# MCU.net
KiCad netlist of a schematic drawn in Altium Designer
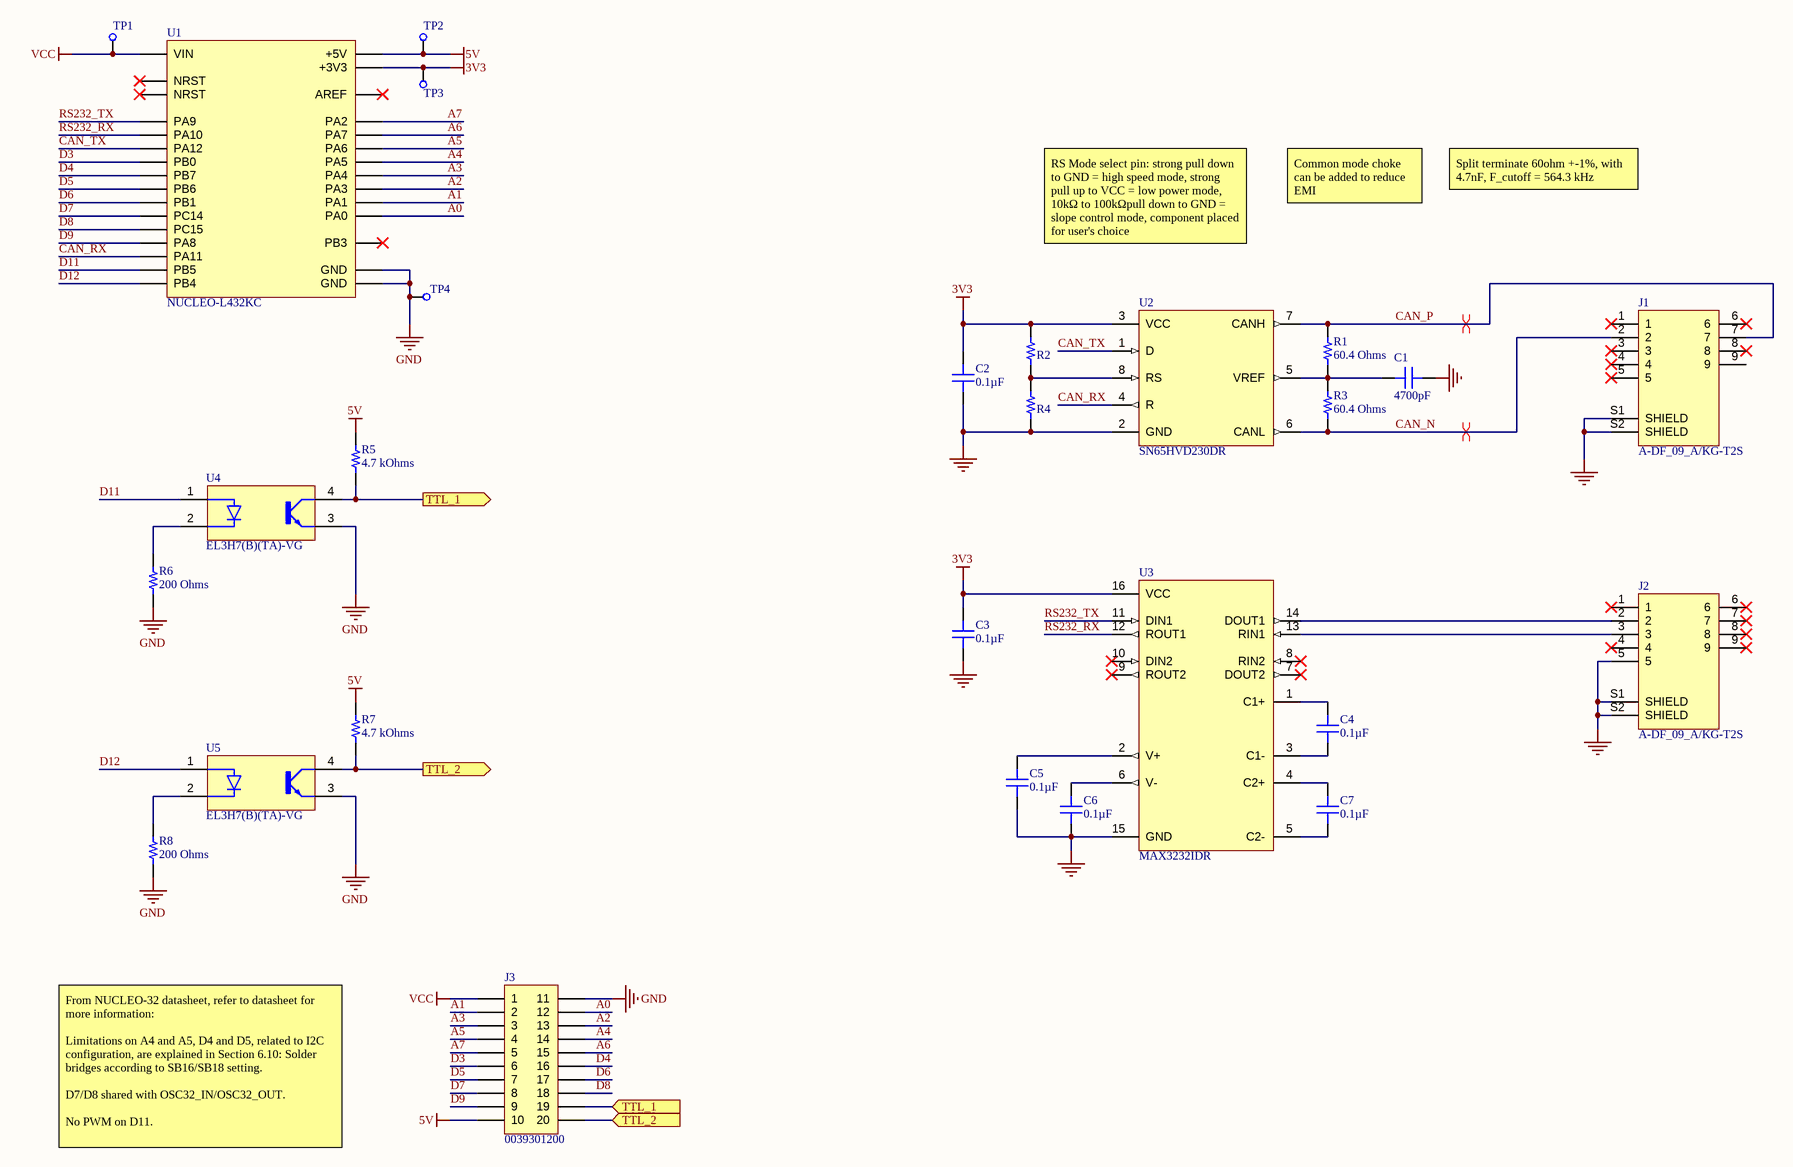
[diagram p0: MCU.SchDoc]

(export (version "E")
  (design (tool "Eeschema 10.0.6"))
  (components
    (comp (ref "C1")
      (value "4700pF")
      (footprint "CAP 0603_1608")
      (description "CAP CER 4700PF 50V X7R 0603")
      (fields
        (field (name "PART NUMBER") "CGA3E2X7R1H472K080AA")
        (field (name "MANUFACTURER") "TDK Corporation")
      )
      (libsource (lib "Celestial Altium Library - altium_library") (part "Capacitor"))
    )
    (comp (ref "C2")
      (value "0.1µF")
      (footprint "CAP 0603_1608")
      (description "CAP CER 0.1UF 25V X7R 0603")
      (fields
        (field (name "PART NUMBER") "CL10B104KA8NNNC")
        (field (name "MANUFACTURER") "Samsung Electro-Mechanics")
      )
      (libsource (lib "Celestial Altium Library - altium_library") (part "Capacitor"))
    )
    (comp (ref "C3")
      (value "0.1µF")
      (footprint "CAP 0603_1608")
      (description "CAP CER 0.1UF 25V X7R 0603")
      (fields
        (field (name "PART NUMBER") "CL10B104KA8NNNC")
        (field (name "MANUFACTURER") "Samsung Electro-Mechanics")
      )
      (libsource (lib "Celestial Altium Library - altium_library") (part "Capacitor"))
    )
    (comp (ref "C4")
      (value "0.1µF")
      (footprint "CAP 0603_1608")
      (description "CAP CER 0.1UF 25V X7R 0603")
      (fields
        (field (name "PART NUMBER") "CL10B104KA8NNNC")
        (field (name "MANUFACTURER") "Samsung Electro-Mechanics")
      )
      (libsource (lib "Celestial Altium Library - altium_library") (part "Capacitor"))
    )
    (comp (ref "C5")
      (value "0.1µF")
      (footprint "CAP 0603_1608")
      (description "CAP CER 0.1UF 25V X7R 0603")
      (fields
        (field (name "PART NUMBER") "CL10B104KA8NNNC")
        (field (name "MANUFACTURER") "Samsung Electro-Mechanics")
      )
      (libsource (lib "Celestial Altium Library - altium_library") (part "Capacitor"))
    )
    (comp (ref "C6")
      (value "0.1µF")
      (footprint "CAP 0603_1608")
      (description "CAP CER 0.1UF 25V X7R 0603")
      (fields
        (field (name "PART NUMBER") "CL10B104KA8NNNC")
        (field (name "MANUFACTURER") "Samsung Electro-Mechanics")
      )
      (libsource (lib "Celestial Altium Library - altium_library") (part "Capacitor"))
    )
    (comp (ref "C7")
      (value "0.1µF")
      (footprint "CAP 0603_1608")
      (description "CAP CER 0.1UF 25V X7R 0603")
      (fields
        (field (name "PART NUMBER") "CL10B104KA8NNNC")
        (field (name "MANUFACTURER") "Samsung Electro-Mechanics")
      )
      (libsource (lib "Celestial Altium Library - altium_library") (part "Capacitor"))
    )
    (comp (ref "J1")
      (value "A-DF_09_A/KG-T2S")
      (footprint "ASSMANN_A-DF09A/KG-T2S")
      (description "Conn D-Subminiature F 9 POS 2.77mm Solder RA Thru-Hole 9 Terminal 1 Port")
      (fields (field (name "MF") "{'manufacturer': u'Assmann WSW'}"))
      (libsource (lib "RTC_Mini_Symbols") (part "A-DF_09_A/KG-T2S"))
    )
    (comp (ref "J2")
      (value "A-DF_09_A/KG-T2S")
      (footprint "ASSMANN_A-DF09A/KG-T2S")
      (description "Conn D-Subminiature F 9 POS 2.77mm Solder RA Thru-Hole 9 Terminal 1 Port")
      (fields (field (name "MF") "{'manufacturer': u'Assmann WSW'}"))
      (libsource (lib "RTC_Mini_Symbols") (part "A-DF_09_A/KG-T2S"))
    )
    (comp (ref "J3")
      (value "0039301200")
      (footprint "MOLEX_0039301200")
      (description "Connector Header Through Hole, Right Angle 20 position 0.165\" (4.20mm)")
      (libsource (lib "RTC_Mini_Symbols") (part "0039301200"))
    )
    (comp (ref "R1")
      (value "60.4 Ohms")
      (footprint "RES 0603_1608")
      (description "RES 60.4 OHM 1% 1/10W 0603")
      (fields
        (field (name "PART NUMBER") "RMCF0603FT60R4")
        (field (name "MANUFACTURER") "Stackpole Electronics Inc")
      )
      (libsource (lib "Celestial Altium Library - altium_library") (part "Resistor"))
    )
    (comp (ref "R2")
      (value "~")
      (footprint "RES 0805_2012")
      (description "RES SMD 0 OHM JUMP 1/8W 0805")
      (fields (field (name "PART NUMBER") "CRCW08050000Z0EAC") (field (name "MANUFACTURER") "Vishay Dale"))
      (libsource (lib "Celestial Altium Library - altium_library") (part "Resistor"))
    )
    (comp (ref "R3")
      (value "60.4 Ohms")
      (footprint "RES 0603_1608")
      (description "RES 60.4 OHM 1% 1/10W 0603")
      (fields
        (field (name "PART NUMBER") "RMCF0603FT60R4")
        (field (name "MANUFACTURER") "Stackpole Electronics Inc")
      )
      (libsource (lib "Celestial Altium Library - altium_library") (part "Resistor"))
    )
    (comp (ref "R4")
      (value "~")
      (footprint "RES 0805_2012")
      (description "RES SMD 0 OHM JUMP 1/8W 0805")
      (fields (field (name "PART NUMBER") "CRCW08050000Z0EAC") (field (name "MANUFACTURER") "Vishay Dale"))
      (libsource (lib "Celestial Altium Library - altium_library") (part "Resistor"))
    )
    (comp (ref "R5")
      (value "4.7 kOhms")
      (footprint "RES 0603_1608")
      (description "RES SMD 4.7K OHM 1% 1/10W 0603")
      (fields (field (name "PART NUMBER") "RC0603FR-074K7L") (field (name "MANUFACTURER") "Yageo"))
      (libsource (lib "Celestial Altium Library - altium_library") (part "Resistor"))
    )
    (comp (ref "R6")
      (value "200 Ohms")
      (footprint "RES 0603_1608")
      (description "RES 200 OHM 5% 1/10W 0603")
      (fields
        (field (name "PART NUMBER") "RMCF0603JT200R")
        (field (name "MANUFACTURER") "Stackpole Electronics Inc")
      )
      (libsource (lib "Celestial Altium Library - altium_library") (part "Resistor"))
    )
    (comp (ref "R7")
      (value "4.7 kOhms")
      (footprint "RES 0603_1608")
      (description "RES SMD 4.7K OHM 1% 1/10W 0603")
      (fields (field (name "PART NUMBER") "RC0603FR-074K7L") (field (name "MANUFACTURER") "Yageo"))
      (libsource (lib "Celestial Altium Library - altium_library") (part "Resistor"))
    )
    (comp (ref "R8")
      (value "200 Ohms")
      (footprint "RES 0603_1608")
      (description "RES 200 OHM 5% 1/10W 0603")
      (fields
        (field (name "PART NUMBER") "RMCF0603JT200R")
        (field (name "MANUFACTURER") "Stackpole Electronics Inc")
      )
      (libsource (lib "Celestial Altium Library - altium_library") (part "Resistor"))
    )
    (comp (ref "TP1")
      (value "Testpoint1")
      (footprint "TESTPOINT40")
      (description "Testpoint 40mil pad")
      (libsource (lib "RTC_Mini_Symbols") (part "Testpoint1"))
    )
    (comp (ref "TP2")
      (value "Testpoint1")
      (footprint "TESTPOINT40")
      (description "Testpoint 40mil pad")
      (libsource (lib "RTC_Mini_Symbols") (part "Testpoint1"))
    )
    (comp (ref "TP3")
      (value "Testpoint1")
      (footprint "TESTPOINT40")
      (description "Testpoint 40mil pad")
      (libsource (lib "RTC_Mini_Symbols") (part "Testpoint1"))
    )
    (comp (ref "TP4")
      (value "Testpoint1")
      (footprint "TESTPOINT40")
      (description "Testpoint 40mil pad")
      (libsource (lib "RTC_Mini_Symbols") (part "Testpoint1"))
    )
    (comp (ref "U1")
      (value "NUCLEO-L432KC")
      (footprint "MODULE_NUCLEO-L432KC")
      (description "STM32 Nucleo-32 development board with STM32L432KC MCU, supports Arduino connectivity")
      (fields (field (name "MF") "{'manufacturer': u'STMicroelectronics'}"))
      (libsource (lib "RTC_Mini_Symbols") (part "NUCLEO-L432KC"))
    )
    (comp (ref "U2")
      (value "SN65HVD230DR")
      (footprint "SOIC127P599X175-8N")
      (description "3.3 V CAN Transceiver with Standby Mode 8-SOIC -40 to 85")
      (fields (field (name "MF") "{'manufacturer': u'Texas Instruments'}"))
      (libsource (lib "RTC_Mini_Symbols") (part "SN65HVD230DR"))
    )
    (comp (ref "U3")
      (value "MAX3232IDR")
      (footprint "SOIC127P600X175-16N")
      (description "3-V to 5.5-V multichannel RS-232 line driver & receiver 16-SOIC -40 to 85")
      (fields (field (name "MF") "{'manufacturer': u'Texas Instruments'}"))
      (libsource (lib "RTC_Mini_Symbols") (part "MAX3232IDR"))
    )
    (comp (ref "U4")
      (value "EL3H7(B)(TA)-VG")
      (footprint "SOIC127P700X200-4N")
      (description "Optoisolator Transistor Output 3750Vrms 1 Channel 4-SSOP")
      (fields (field (name "MP") "EL3H7-G") (field (name "MF") "{'manufacturer': u'Everlight Electronics'}"))
      (libsource (lib "RTC_Mini_Symbols") (part "EL3H7(B)(TA)-VG"))
    )
    (comp (ref "U5")
      (value "EL3H7(B)(TA)-VG")
      (footprint "SOIC127P700X200-4N")
      (description "Optoisolator Transistor Output 3750Vrms 1 Channel 4-SSOP")
      (fields (field (name "MP") "EL3H7-G") (field (name "MF") "{'manufacturer': u'Everlight Electronics'}"))
      (libsource (lib "RTC_Mini_Symbols") (part "EL3H7(B)(TA)-VG"))
    )
  )
  (nets
    (net (code "1") (name "/A0") (class "Default")
      (node (ref "J3") (pin "12") (pinfunction "12_12") (pintype "passive"))
      (node (ref "U1") (pin "CN4_12") (pinfunction "PA0_CN4_12") (pintype "passive"))
    )
    (net (code "2") (name "/A1") (class "Default")
      (node (ref "J3") (pin "2") (pinfunction "2_2") (pintype "passive"))
      (node (ref "U1") (pin "CN4_11") (pinfunction "PA1_CN4_11") (pintype "passive"))
    )
    (net (code "3") (name "/A2") (class "Default")
      (node (ref "J3") (pin "13") (pinfunction "13_13") (pintype "passive"))
      (node (ref "U1") (pin "CN4_10") (pinfunction "PA3_CN4_10") (pintype "passive"))
    )
    (net (code "4") (name "/A3") (class "Default")
      (node (ref "J3") (pin "3") (pinfunction "3_3") (pintype "passive"))
      (node (ref "U1") (pin "CN4_9") (pinfunction "PA4_CN4_9") (pintype "passive"))
    )
    (net (code "5") (name "/A4") (class "Default")
      (node (ref "J3") (pin "14") (pinfunction "14_14") (pintype "passive"))
      (node (ref "U1") (pin "CN4_8") (pinfunction "PA5_CN4_8") (pintype "passive"))
    )
    (net (code "6") (name "/A5") (class "Default")
      (node (ref "J3") (pin "4") (pinfunction "4_4") (pintype "passive"))
      (node (ref "U1") (pin "CN4_7") (pinfunction "PA6_CN4_7") (pintype "passive"))
    )
    (net (code "7") (name "/A6") (class "Default")
      (node (ref "J3") (pin "15") (pinfunction "15_15") (pintype "passive"))
      (node (ref "U1") (pin "CN4_6") (pinfunction "PA7_CN4_6") (pintype "passive"))
    )
    (net (code "8") (name "/A7") (class "Default")
      (node (ref "J3") (pin "5") (pinfunction "5_5") (pintype "passive"))
      (node (ref "U1") (pin "CN4_5") (pinfunction "PA2_CN4_5") (pintype "passive"))
    )
    (net (code "9") (name "/CAN_N") (class "Default")
      (node (ref "J1") (pin "2") (pinfunction "2_2") (pintype "passive"))
      (node (ref "R3") (pin "2") (pinfunction "2_2") (pintype "passive"))
      (node (ref "U2") (pin "6") (pinfunction "CANL_6") (pintype "output"))
    )
    (net (code "10") (name "/CAN_P") (class "Default")
      (node (ref "J1") (pin "7") (pinfunction "7_7") (pintype "passive"))
      (node (ref "R1") (pin "1") (pinfunction "1_1") (pintype "passive"))
      (node (ref "U2") (pin "7") (pinfunction "CANH_7") (pintype "output"))
    )
    (net (code "11") (name "/CAN_RX") (class "Default")
      (node (ref "U1") (pin "CN3_13") (pinfunction "PA11_CN3_13") (pintype "passive"))
      (node (ref "U2") (pin "4") (pinfunction "R_4") (pintype "output"))
    )
    (net (code "12") (name "/CAN_TX") (class "Default")
      (node (ref "U1") (pin "CN3_5") (pinfunction "PA12_CN3_5") (pintype "passive"))
      (node (ref "U2") (pin "1") (pinfunction "D_1") (pintype "input"))
    )
    (net (code "13") (name "/D3") (class "Default")
      (node (ref "J3") (pin "6") (pinfunction "6_6") (pintype "passive"))
      (node (ref "U1") (pin "CN3_6") (pinfunction "PB0_CN3_6") (pintype "passive"))
    )
    (net (code "14") (name "/D4") (class "Default")
      (node (ref "J3") (pin "16") (pinfunction "16_16") (pintype "passive"))
      (node (ref "U1") (pin "CN3_7") (pinfunction "PB7_CN3_7") (pintype "passive"))
    )
    (net (code "15") (name "/D5") (class "Default")
      (node (ref "J3") (pin "7") (pinfunction "7_7") (pintype "passive"))
      (node (ref "U1") (pin "CN3_8") (pinfunction "PB6_CN3_8") (pintype "passive"))
    )
    (net (code "16") (name "/D6") (class "Default")
      (node (ref "J3") (pin "17") (pinfunction "17_17") (pintype "passive"))
      (node (ref "U1") (pin "CN3_9") (pinfunction "PB1_CN3_9") (pintype "passive"))
    )
    (net (code "17") (name "/D7") (class "Default")
      (node (ref "J3") (pin "8") (pinfunction "8_8") (pintype "passive"))
      (node (ref "U1") (pin "CN3_10") (pinfunction "PC14_CN3_10") (pintype "passive"))
    )
    (net (code "18") (name "/D8") (class "Default")
      (node (ref "J3") (pin "18") (pinfunction "18_18") (pintype "passive"))
      (node (ref "U1") (pin "CN3_11") (pinfunction "PC15_CN3_11") (pintype "passive"))
    )
    (net (code "19") (name "/D9") (class "Default")
      (node (ref "J3") (pin "9") (pinfunction "9_9") (pintype "passive"))
      (node (ref "U1") (pin "CN3_12") (pinfunction "PA8_CN3_12") (pintype "passive"))
    )
    (net (code "20") (name "/D11") (class "Default")
      (node (ref "U1") (pin "CN3_14") (pinfunction "PB5_CN3_14") (pintype "passive"))
      (node (ref "U4") (pin "1") (pinfunction "A_1") (pintype "passive"))
    )
    (net (code "21") (name "/D12") (class "Default")
      (node (ref "U1") (pin "CN3_15") (pinfunction "PB4_CN3_15") (pintype "passive"))
      (node (ref "U5") (pin "1") (pinfunction "A_1") (pintype "passive"))
    )
    (net (code "22") (name "/RS232_RX") (class "Default")
      (node (ref "U1") (pin "CN3_2") (pinfunction "PA10_CN3_2") (pintype "passive"))
      (node (ref "U3") (pin "12") (pinfunction "ROUT1_12") (pintype "output"))
    )
    (net (code "23") (name "/RS232_TX") (class "Default")
      (node (ref "U1") (pin "CN3_1") (pinfunction "PA9_CN3_1") (pintype "passive"))
      (node (ref "U3") (pin "11") (pinfunction "DIN1_11") (pintype "input"))
    )
    (net (code "24") (name "/TTL_1") (class "Default")
      (node (ref "J3") (pin "19") (pinfunction "19_19") (pintype "passive"))
      (node (ref "R5") (pin "2") (pinfunction "2_2") (pintype "passive"))
      (node (ref "U4") (pin "4") (pinfunction "CO_4") (pintype "passive"))
    )
    (net (code "25") (name "/TTL_2") (class "Default")
      (node (ref "J3") (pin "20") (pinfunction "20_20") (pintype "passive"))
      (node (ref "R7") (pin "2") (pinfunction "2_2") (pintype "passive"))
      (node (ref "U5") (pin "4") (pinfunction "CO_4") (pintype "passive"))
    )
    (net (code "26") (name "3V3") (class "Default")
      (node (ref "C2") (pin "2") (pinfunction "2_2") (pintype "passive"))
      (node (ref "C3") (pin "2") (pinfunction "2_2") (pintype "passive"))
      (node (ref "R2") (pin "2") (pinfunction "2_2") (pintype "passive"))
      (node (ref "TP3") (pin "1") (pinfunction "1_1") (pintype "passive"))
      (node (ref "U1") (pin "CN4_14") (pinfunction "+3V3_CN4_14") (pintype "power_in"))
      (node (ref "U2") (pin "3") (pinfunction "VCC_3") (pintype "power_in"))
      (node (ref "U3") (pin "16") (pinfunction "VCC_16") (pintype "power_in"))
    )
    (net (code "27") (name "5V") (class "Default")
      (node (ref "J3") (pin "10") (pinfunction "10_10") (pintype "passive"))
      (node (ref "R5") (pin "1") (pinfunction "1_1") (pintype "passive"))
      (node (ref "R7") (pin "1") (pinfunction "1_1") (pintype "passive"))
      (node (ref "TP2") (pin "1") (pinfunction "1_1") (pintype "passive"))
      (node (ref "U1") (pin "CN4_4") (pinfunction "+5V_CN4_4") (pintype "power_in"))
    )
    (net (code "28") (name "GND") (class "Default")
      (node (ref "C1") (pin "2") (pinfunction "2_2") (pintype "passive"))
      (node (ref "C2") (pin "1") (pinfunction "1_1") (pintype "passive"))
      (node (ref "C3") (pin "1") (pinfunction "1_1") (pintype "passive"))
      (node (ref "C5") (pin "1") (pinfunction "1_1") (pintype "passive"))
      (node (ref "C6") (pin "1") (pinfunction "1_1") (pintype "passive"))
      (node (ref "J1") (pin "S1") (pinfunction "SHIELD_S1") (pintype "passive"))
      (node (ref "J1") (pin "S2") (pinfunction "SHIELD_S2") (pintype "passive"))
      (node (ref "J2") (pin "5") (pinfunction "5_5") (pintype "passive"))
      (node (ref "J2") (pin "S1") (pinfunction "SHIELD_S1") (pintype "passive"))
      (node (ref "J2") (pin "S2") (pinfunction "SHIELD_S2") (pintype "passive"))
      (node (ref "J3") (pin "11") (pinfunction "11_11") (pintype "passive"))
      (node (ref "R4") (pin "1") (pinfunction "1_1") (pintype "passive"))
      (node (ref "R6") (pin "1") (pinfunction "1_1") (pintype "passive"))
      (node (ref "R8") (pin "1") (pinfunction "1_1") (pintype "passive"))
      (node (ref "TP4") (pin "1") (pinfunction "1_1") (pintype "passive"))
      (node (ref "U1") (pin "CN3_4") (pinfunction "GND_CN3_4") (pintype "power_in"))
      (node (ref "U1") (pin "CN4_2") (pinfunction "GND_CN4_2") (pintype "power_in"))
      (node (ref "U2") (pin "2") (pinfunction "GND_2") (pintype "power_in"))
      (node (ref "U3") (pin "15") (pinfunction "GND_15") (pintype "power_in"))
      (node (ref "U4") (pin "3") (pinfunction "E_3") (pintype "passive"))
      (node (ref "U5") (pin "3") (pinfunction "E_3") (pintype "passive"))
    )
    (net (code "29") (name "Net-(U2-RS)") (class "Default")
      (node (ref "R2") (pin "1") (pinfunction "1_1") (pintype "passive"))
      (node (ref "R4") (pin "2") (pinfunction "2_2") (pintype "passive"))
      (node (ref "U2") (pin "8") (pinfunction "RS_8") (pintype "input"))
    )
    (net (code "30") (name "Net-(U2-VREF)") (class "Default")
      (node (ref "C1") (pin "1") (pinfunction "1_1") (pintype "passive"))
      (node (ref "R1") (pin "2") (pinfunction "2_2") (pintype "passive"))
      (node (ref "R3") (pin "1") (pinfunction "1_1") (pintype "passive"))
      (node (ref "U2") (pin "5") (pinfunction "VREF_5") (pintype "output"))
    )
    (net (code "31") (name "Net-(U3-C1+)") (class "Default")
      (node (ref "C4") (pin "2") (pinfunction "2_2") (pintype "passive"))
      (node (ref "U3") (pin "1") (pinfunction "C1+_1") (pintype "passive"))
    )
    (net (code "32") (name "Net-(U3-C1-)") (class "Default")
      (node (ref "C4") (pin "1") (pinfunction "1_1") (pintype "passive"))
      (node (ref "U3") (pin "3") (pinfunction "C1-_3") (pintype "passive"))
    )
    (net (code "33") (name "Net-(U3-C2+)") (class "Default")
      (node (ref "C7") (pin "2") (pinfunction "2_2") (pintype "passive"))
      (node (ref "U3") (pin "4") (pinfunction "C2+_4") (pintype "passive"))
    )
    (net (code "34") (name "Net-(U3-C2-)") (class "Default")
      (node (ref "C7") (pin "1") (pinfunction "1_1") (pintype "passive"))
      (node (ref "U3") (pin "5") (pinfunction "C2-_5") (pintype "passive"))
    )
    (net (code "35") (name "Net-(U3-DOUT1)") (class "Default")
      (node (ref "J2") (pin "2") (pinfunction "2_2") (pintype "passive"))
      (node (ref "U3") (pin "14") (pinfunction "DOUT1_14") (pintype "output"))
    )
    (net (code "36") (name "Net-(U3-RIN1)") (class "Default")
      (node (ref "J2") (pin "3") (pinfunction "3_3") (pintype "passive"))
      (node (ref "U3") (pin "13") (pinfunction "RIN1_13") (pintype "input"))
    )
    (net (code "37") (name "Net-(U3-V+)") (class "Default")
      (node (ref "C5") (pin "2") (pinfunction "2_2") (pintype "passive"))
      (node (ref "U3") (pin "2") (pinfunction "V+_2") (pintype "output"))
    )
    (net (code "38") (name "Net-(U3-V-)") (class "Default")
      (node (ref "C6") (pin "2") (pinfunction "2_2") (pintype "passive"))
      (node (ref "U3") (pin "6") (pinfunction "V-_6") (pintype "output"))
    )
    (net (code "39") (name "Net-(U4-C)") (class "Default")
      (node (ref "R6") (pin "2") (pinfunction "2_2") (pintype "passive"))
      (node (ref "U4") (pin "2") (pinfunction "C_2") (pintype "passive"))
    )
    (net (code "40") (name "Net-(U5-C)") (class "Default")
      (node (ref "R8") (pin "2") (pinfunction "2_2") (pintype "passive"))
      (node (ref "U5") (pin "2") (pinfunction "C_2") (pintype "passive"))
    )
    (net (code "41") (name "VCC") (class "Default")
      (node (ref "J3") (pin "1") (pinfunction "1_1") (pintype "passive"))
      (node (ref "TP1") (pin "1") (pinfunction "1_1") (pintype "passive"))
      (node (ref "U1") (pin "CN4_1") (pinfunction "VIN_CN4_1") (pintype "power_in"))
    )
    (net (code "42") (name "unconnected-(J1-Pad1)") (class "Default")
      (node (ref "J1") (pin "1") (pinfunction "1_1") (pintype "passive+no_connect"))
    )
    (net (code "43") (name "unconnected-(J1-Pad3)") (class "Default")
      (node (ref "J1") (pin "3") (pinfunction "3_3") (pintype "passive+no_connect"))
    )
    (net (code "44") (name "unconnected-(J1-Pad4)") (class "Default")
      (node (ref "J1") (pin "4") (pinfunction "4_4") (pintype "passive+no_connect"))
    )
    (net (code "45") (name "unconnected-(J1-Pad5)") (class "Default")
      (node (ref "J1") (pin "5") (pinfunction "5_5") (pintype "passive+no_connect"))
    )
    (net (code "46") (name "unconnected-(J1-Pad6)") (class "Default")
      (node (ref "J1") (pin "6") (pinfunction "6_6") (pintype "passive+no_connect"))
    )
    (net (code "47") (name "unconnected-(J1-Pad8)") (class "Default")
      (node (ref "J1") (pin "8") (pinfunction "8_8") (pintype "passive+no_connect"))
    )
    (net (code "48") (name "unconnected-(J1-Pad9)") (class "Default")
      (node (ref "J1") (pin "9") (pinfunction "9_9") (pintype "passive"))
    )
    (net (code "49") (name "unconnected-(J2-Pad1)") (class "Default")
      (node (ref "J2") (pin "1") (pinfunction "1_1") (pintype "passive+no_connect"))
    )
    (net (code "50") (name "unconnected-(J2-Pad4)") (class "Default")
      (node (ref "J2") (pin "4") (pinfunction "4_4") (pintype "passive+no_connect"))
    )
    (net (code "51") (name "unconnected-(J2-Pad6)") (class "Default")
      (node (ref "J2") (pin "6") (pinfunction "6_6") (pintype "passive+no_connect"))
    )
    (net (code "52") (name "unconnected-(J2-Pad7)") (class "Default")
      (node (ref "J2") (pin "7") (pinfunction "7_7") (pintype "passive+no_connect"))
    )
    (net (code "53") (name "unconnected-(J2-Pad8)") (class "Default")
      (node (ref "J2") (pin "8") (pinfunction "8_8") (pintype "passive+no_connect"))
    )
    (net (code "54") (name "unconnected-(J2-Pad9)") (class "Default")
      (node (ref "J2") (pin "9") (pinfunction "9_9") (pintype "passive+no_connect"))
    )
    (net (code "55") (name "unconnected-(U1-AREF-PadCN4_13)") (class "Default")
      (node (ref "U1") (pin "CN4_13") (pinfunction "AREF_CN4_13") (pintype "passive+no_connect"))
    )
    (net (code "56") (name "unconnected-(U1-NRST-PadCN3_3)") (class "Default")
      (node (ref "U1") (pin "CN3_3") (pinfunction "NRST_CN3_3") (pintype "passive+no_connect"))
    )
    (net (code "57") (name "unconnected-(U1-NRST-PadCN4_3)") (class "Default")
      (node (ref "U1") (pin "CN4_3") (pinfunction "NRST_CN4_3") (pintype "passive+no_connect"))
    )
    (net (code "58") (name "unconnected-(U1-PB3-PadCN4_15)") (class "Default")
      (node (ref "U1") (pin "CN4_15") (pinfunction "PB3_CN4_15") (pintype "passive+no_connect"))
    )
    (net (code "59") (name "unconnected-(U3-DIN2-Pad10)") (class "Default")
      (node (ref "U3") (pin "10") (pinfunction "DIN2_10") (pintype "input+no_connect"))
    )
    (net (code "60") (name "unconnected-(U3-DOUT2-Pad7)") (class "Default")
      (node (ref "U3") (pin "7") (pinfunction "DOUT2_7") (pintype "output+no_connect"))
    )
    (net (code "61") (name "unconnected-(U3-RIN2-Pad8)") (class "Default")
      (node (ref "U3") (pin "8") (pinfunction "RIN2_8") (pintype "input+no_connect"))
    )
    (net (code "62") (name "unconnected-(U3-ROUT2-Pad9)") (class "Default")
      (node (ref "U3") (pin "9") (pinfunction "ROUT2_9") (pintype "output+no_connect"))
    )
  )
)
